# OSSI-1_OBC_0.net
KiCad netlist of a schematic drawn in Altium Designer
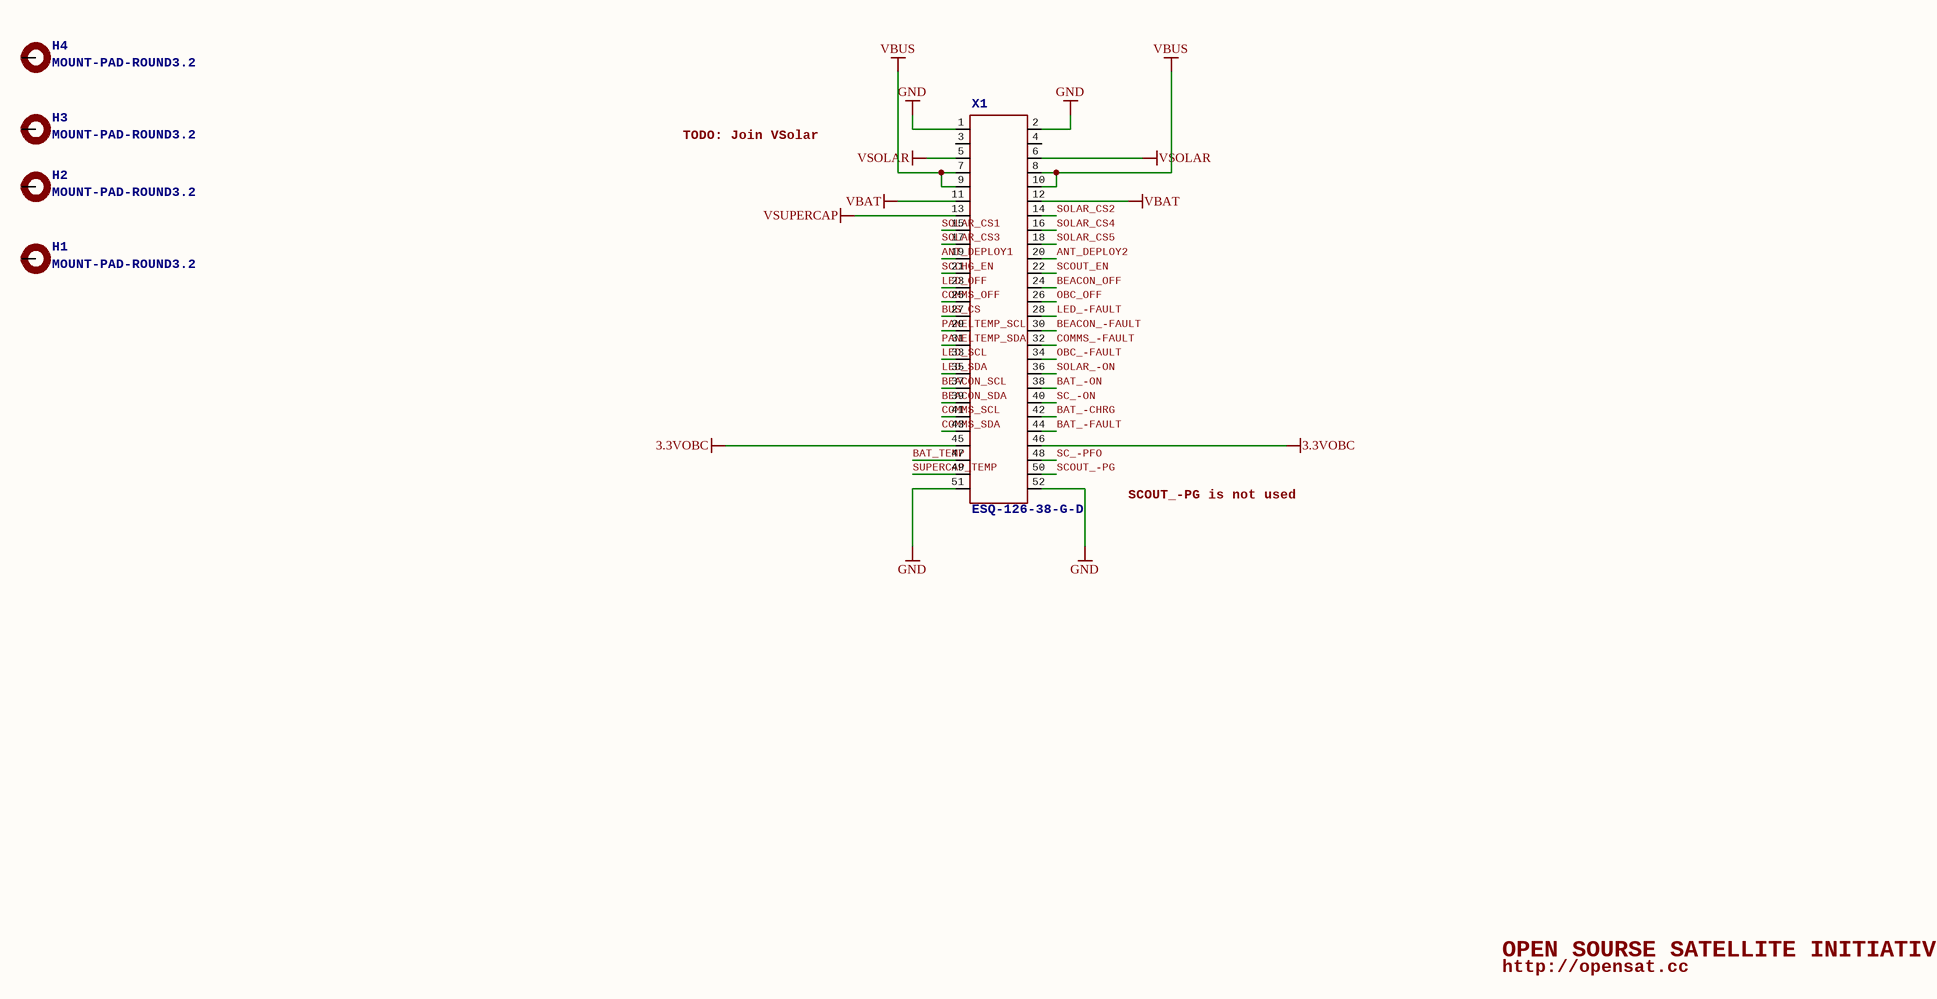
[diagram p0: OSSI-1 OBC_0.SchDoc]

(export (version "E")
  (design (tool "Eeschema 10.0.6"))
  (components
    (comp (ref "H1")
      (value "MOUNT-PAD-ROUND3.2")
      (footprint "3.2-PAD-ROUND")
      (fields (field (name ">NAME") "H1") (field (name ">VALUE") "MOUNT-PAD-ROUND3.2"))
      (libsource (lib "OSSI") (part "MOUNT-PAD-ROUND3.2"))
    )
    (comp (ref "H2")
      (value "MOUNT-PAD-ROUND3.2")
      (footprint "3.2-PAD-ROUND")
      (fields (field (name ">NAME") "H2") (field (name ">VALUE") "MOUNT-PAD-ROUND3.2"))
      (libsource (lib "OSSI") (part "MOUNT-PAD-ROUND3.2"))
    )
    (comp (ref "H3")
      (value "MOUNT-PAD-ROUND3.2")
      (footprint "3.2-PAD-ROUND")
      (fields (field (name ">NAME") "H3") (field (name ">VALUE") "MOUNT-PAD-ROUND3.2"))
      (libsource (lib "OSSI") (part "MOUNT-PAD-ROUND3.2"))
    )
    (comp (ref "H4")
      (value "MOUNT-PAD-ROUND3.2")
      (footprint "3.2-PAD-ROUND")
      (fields (field (name ">NAME") "H4") (field (name ">VALUE") "MOUNT-PAD-ROUND3.2"))
      (libsource (lib "OSSI") (part "MOUNT-PAD-ROUND3.2"))
    )
    (comp (ref "X1")
      (value "ESQ-126-38-G-D")
      (footprint "ESQ-126-XX-X-D")
      (fields (field (name ">NAME") "X1") (field (name ">VALUE") "ESQ-126-38-G-D"))
      (libsource (lib "OSSI") (part "ESQ-126-38-G-D"))
    )
  )
  (nets
    (net (code "1") (name "/ANT_DEPLOY1") (class "Default")
      (node (ref "X1") (pin "19") (pinfunction "19_19") (pintype "passive"))
    )
    (net (code "2") (name "/ANT_DEPLOY2") (class "Default")
      (node (ref "X1") (pin "20") (pinfunction "20_20") (pintype "passive"))
    )
    (net (code "3") (name "/BAT_-CHRG") (class "Default")
      (node (ref "X1") (pin "42") (pinfunction "42_42") (pintype "passive"))
    )
    (net (code "4") (name "/BAT_-FAULT") (class "Default")
      (node (ref "X1") (pin "44") (pinfunction "44_44") (pintype "passive"))
    )
    (net (code "5") (name "/BAT_-ON") (class "Default")
      (node (ref "X1") (pin "38") (pinfunction "38_38") (pintype "passive"))
    )
    (net (code "6") (name "/BAT_TEMP") (class "Default")
      (node (ref "X1") (pin "47") (pinfunction "47_47") (pintype "passive"))
    )
    (net (code "7") (name "/BEACON_-FAULT") (class "Default")
      (node (ref "X1") (pin "30") (pinfunction "30_30") (pintype "passive"))
    )
    (net (code "8") (name "/BEACON_OFF") (class "Default")
      (node (ref "X1") (pin "24") (pinfunction "24_24") (pintype "passive"))
    )
    (net (code "9") (name "/BEACON_SCL") (class "Default")
      (node (ref "X1") (pin "37") (pinfunction "37_37") (pintype "passive"))
    )
    (net (code "10") (name "/BEACON_SDA") (class "Default")
      (node (ref "X1") (pin "39") (pinfunction "39_39") (pintype "passive"))
    )
    (net (code "11") (name "/BUS_CS") (class "Default")
      (node (ref "X1") (pin "27") (pinfunction "27_27") (pintype "passive"))
    )
    (net (code "12") (name "/COMMS_-FAULT") (class "Default")
      (node (ref "X1") (pin "32") (pinfunction "32_32") (pintype "passive"))
    )
    (net (code "13") (name "/COMMS_OFF") (class "Default")
      (node (ref "X1") (pin "25") (pinfunction "25_25") (pintype "passive"))
    )
    (net (code "14") (name "/COMMS_SCL") (class "Default")
      (node (ref "X1") (pin "41") (pinfunction "41_41") (pintype "passive"))
    )
    (net (code "15") (name "/COMMS_SDA") (class "Default")
      (node (ref "X1") (pin "43") (pinfunction "43_43") (pintype "passive"))
    )
    (net (code "16") (name "/LED_-FAULT") (class "Default")
      (node (ref "X1") (pin "28") (pinfunction "28_28") (pintype "passive"))
    )
    (net (code "17") (name "/LED_OFF") (class "Default")
      (node (ref "X1") (pin "23") (pinfunction "23_23") (pintype "passive"))
    )
    (net (code "18") (name "/LED_SCL") (class "Default")
      (node (ref "X1") (pin "33") (pinfunction "33_33") (pintype "passive"))
    )
    (net (code "19") (name "/LED_SDA") (class "Default")
      (node (ref "X1") (pin "35") (pinfunction "35_35") (pintype "passive"))
    )
    (net (code "20") (name "/OBC_-FAULT") (class "Default")
      (node (ref "X1") (pin "34") (pinfunction "34_34") (pintype "passive"))
    )
    (net (code "21") (name "/OBC_OFF") (class "Default")
      (node (ref "X1") (pin "26") (pinfunction "26_26") (pintype "passive"))
    )
    (net (code "22") (name "/PANELTEMP_SCL") (class "Default")
      (node (ref "X1") (pin "29") (pinfunction "29_29") (pintype "passive"))
    )
    (net (code "23") (name "/PANELTEMP_SDA") (class "Default")
      (node (ref "X1") (pin "31") (pinfunction "31_31") (pintype "passive"))
    )
    (net (code "24") (name "/SCCHG_EN") (class "Default")
      (node (ref "X1") (pin "21") (pinfunction "21_21") (pintype "passive"))
    )
    (net (code "25") (name "/SCOUT_-PG") (class "Default")
      (node (ref "X1") (pin "50") (pinfunction "50_50") (pintype "passive"))
    )
    (net (code "26") (name "/SCOUT_EN") (class "Default")
      (node (ref "X1") (pin "22") (pinfunction "22_22") (pintype "passive"))
    )
    (net (code "27") (name "/SC_-ON") (class "Default")
      (node (ref "X1") (pin "40") (pinfunction "40_40") (pintype "passive"))
    )
    (net (code "28") (name "/SC_-PFO") (class "Default")
      (node (ref "X1") (pin "48") (pinfunction "48_48") (pintype "passive"))
    )
    (net (code "29") (name "/SOLAR_-ON") (class "Default")
      (node (ref "X1") (pin "36") (pinfunction "36_36") (pintype "passive"))
    )
    (net (code "30") (name "/SOLAR_CS1") (class "Default")
      (node (ref "X1") (pin "15") (pinfunction "15_15") (pintype "passive"))
    )
    (net (code "31") (name "/SOLAR_CS2") (class "Default")
      (node (ref "X1") (pin "14") (pinfunction "14_14") (pintype "passive"))
    )
    (net (code "32") (name "/SOLAR_CS3") (class "Default")
      (node (ref "X1") (pin "17") (pinfunction "17_17") (pintype "passive"))
    )
    (net (code "33") (name "/SOLAR_CS4") (class "Default")
      (node (ref "X1") (pin "16") (pinfunction "16_16") (pintype "passive"))
    )
    (net (code "34") (name "/SOLAR_CS5") (class "Default")
      (node (ref "X1") (pin "18") (pinfunction "18_18") (pintype "passive"))
    )
    (net (code "35") (name "/SUPERCAP_TEMP") (class "Default")
      (node (ref "X1") (pin "49") (pinfunction "49_49") (pintype "passive"))
    )
    (net (code "36") (name "3.3VOBC") (class "Default")
      (node (ref "X1") (pin "45") (pinfunction "45_45") (pintype "passive"))
      (node (ref "X1") (pin "46") (pinfunction "46_46") (pintype "passive"))
    )
    (net (code "37") (name "GND") (class "Default")
      (node (ref "X1") (pin "1") (pinfunction "1_1") (pintype "passive"))
      (node (ref "X1") (pin "2") (pinfunction "2_2") (pintype "passive"))
      (node (ref "X1") (pin "51") (pinfunction "51_51") (pintype "passive"))
      (node (ref "X1") (pin "52") (pinfunction "52_52") (pintype "passive"))
    )
    (net (code "38") (name "VBAT") (class "Default")
      (node (ref "X1") (pin "11") (pinfunction "11_11") (pintype "passive"))
      (node (ref "X1") (pin "12") (pinfunction "12_12") (pintype "passive"))
    )
    (net (code "39") (name "VBUS") (class "Default")
      (node (ref "X1") (pin "10") (pinfunction "10_10") (pintype "passive"))
      (node (ref "X1") (pin "7") (pinfunction "7_7") (pintype "passive"))
      (node (ref "X1") (pin "8") (pinfunction "8_8") (pintype "passive"))
      (node (ref "X1") (pin "9") (pinfunction "9_9") (pintype "passive"))
    )
    (net (code "40") (name "VSOLAR") (class "Default")
      (node (ref "X1") (pin "5") (pinfunction "5_5") (pintype "passive"))
      (node (ref "X1") (pin "6") (pinfunction "6_6") (pintype "passive"))
    )
    (net (code "41") (name "VSUPERCAP") (class "Default")
      (node (ref "X1") (pin "13") (pinfunction "13_13") (pintype "passive"))
    )
    (net (code "42") (name "unconnected-(H1-MOUNT-PadB3)") (class "Default")
      (node (ref "H1") (pin "B3") (pinfunction "MOUNT_B3") (pintype "passive"))
      (node (ref "H1") (pin "2") (pinfunction "MOUNT_2") (pintype "passive"))
    )
    (net (code "43") (name "unconnected-(H2-MOUNT-PadB3)") (class "Default")
      (node (ref "H2") (pin "B3") (pinfunction "MOUNT_B3") (pintype "passive"))
      (node (ref "H2") (pin "2") (pinfunction "MOUNT_2") (pintype "passive"))
    )
    (net (code "44") (name "unconnected-(H3-MOUNT-PadB3)") (class "Default")
      (node (ref "H3") (pin "B3") (pinfunction "MOUNT_B3") (pintype "passive"))
      (node (ref "H3") (pin "2") (pinfunction "MOUNT_2") (pintype "passive"))
    )
    (net (code "45") (name "unconnected-(H4-MOUNT-PadB3)") (class "Default")
      (node (ref "H4") (pin "B3") (pinfunction "MOUNT_B3") (pintype "passive"))
      (node (ref "H4") (pin "2") (pinfunction "MOUNT_2") (pintype "passive"))
    )
    (net (code "46") (name "unconnected-(X1-Pad3)") (class "Default")
      (node (ref "X1") (pin "3") (pinfunction "3_3") (pintype "passive"))
    )
    (net (code "47") (name "unconnected-(X1-Pad4)") (class "Default")
      (node (ref "X1") (pin "4") (pinfunction "4_4") (pintype "passive"))
    )
  )
)
